# 1-7.net
KiCad netlist of a schematic drawn in EAGLE
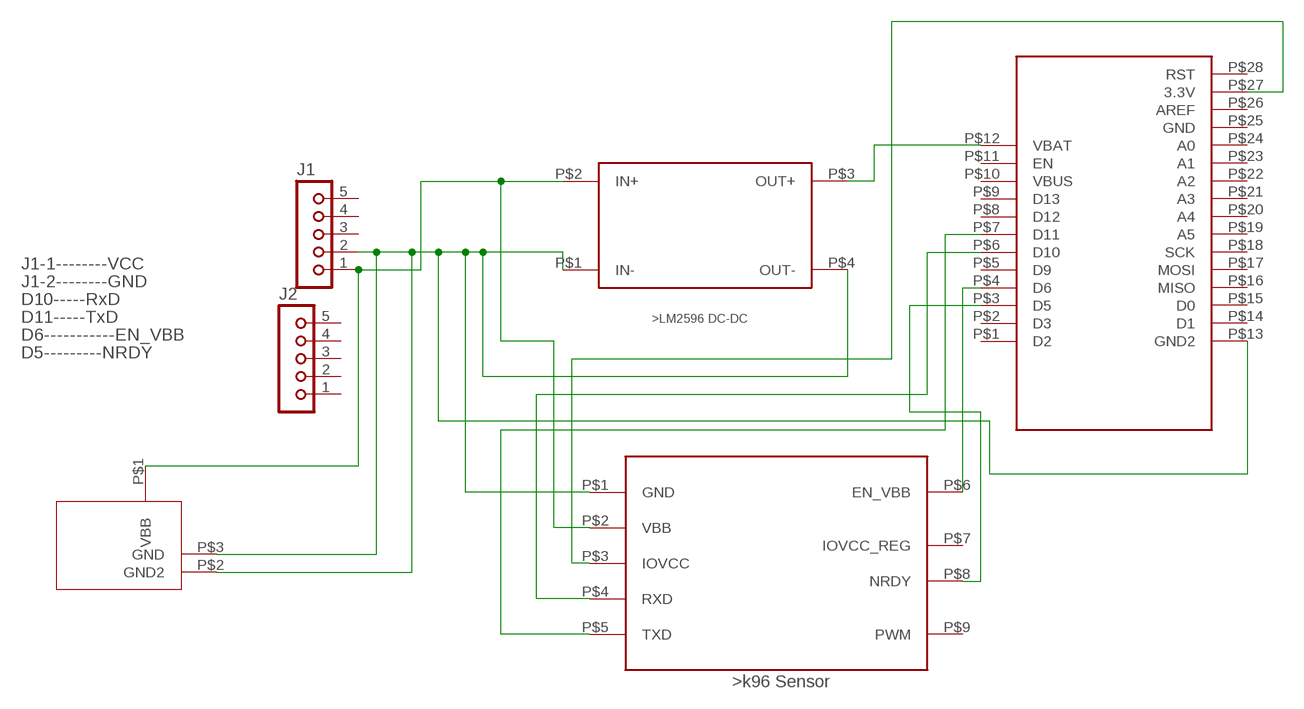
[diagram p0: schematic, sheet 1]

(export (version "E")
  (design (tool "Eeschema 10.0.6"))
  (components
    (comp (ref "DCDC1")
      (value "DCDC")
      (footprint "eagle-import:DCDC")
      (libsource (lib "eagle-import") (part "DCDC"))
    )
    (comp (ref "FEATHER1")
      (value "FEATHER")
      (footprint "eagle-import:FEATHER")
      (libsource (lib "eagle-import") (part "FEATHER"))
    )
    (comp (ref "J1")
      (value "JU05")
      (footprint "eagle-import:JU05")
      (libsource (lib "eagle-import") (part "JU05"))
    )
    (comp (ref "J2")
      (value "JU05")
      (footprint "eagle-import:JU05")
      (libsource (lib "eagle-import") (part "JU05"))
    )
    (comp (ref "K96SENSOR1")
      (value "K96SENSOR")
      (footprint "eagle-import:K96SENSOR")
      (libsource (lib "eagle-import") (part "K96SENSOR"))
    )
    (comp (ref "U$1")
      (value "POWER")
      (footprint "eagle-import:POWERIN")
      (libsource (lib "eagle-import") (part "POWER"))
    )
  )
  (nets
    (net (code "1") (name "Net-(DCDC1-IN+)") (class "Default")
      (node (ref "DCDC1") (pin "P$2") (pinfunction "IN+_P$2") (pintype "bidirectional"))
      (node (ref "J1") (pin "1") (pinfunction "1_1") (pintype "passive"))
      (node (ref "K96SENSOR1") (pin "P$2") (pinfunction "VBB_P$2") (pintype "bidirectional"))
      (node (ref "U$1") (pin "P$1") (pinfunction "VBB_P$1") (pintype "bidirectional"))
    )
    (net (code "2") (name "Net-(DCDC1-IN-)") (class "Default")
      (node (ref "DCDC1") (pin "P$1") (pinfunction "IN-_P$1") (pintype "bidirectional"))
      (node (ref "DCDC1") (pin "P$4") (pinfunction "OUT-_P$4") (pintype "bidirectional"))
      (node (ref "FEATHER1") (pin "P$13") (pinfunction "GND2_P$13") (pintype "bidirectional"))
      (node (ref "J1") (pin "2") (pinfunction "2_2") (pintype "passive"))
      (node (ref "K96SENSOR1") (pin "P$1") (pinfunction "GND_P$1") (pintype "bidirectional"))
      (node (ref "U$1") (pin "P$2") (pinfunction "GND2_P$2") (pintype "bidirectional"))
      (node (ref "U$1") (pin "P$3") (pinfunction "GND_P$3") (pintype "bidirectional"))
    )
    (net (code "3") (name "Net-(DCDC1-OUT+)") (class "Default")
      (node (ref "DCDC1") (pin "P$3") (pinfunction "OUT+_P$3") (pintype "bidirectional"))
      (node (ref "FEATHER1") (pin "P$12") (pinfunction "VBAT_P$12") (pintype "bidirectional"))
    )
    (net (code "4") (name "Net-(FEATHER1-3.3V)") (class "Default")
      (node (ref "FEATHER1") (pin "P$27") (pinfunction "3.3V_P$27") (pintype "bidirectional"))
      (node (ref "K96SENSOR1") (pin "P$3") (pinfunction "IOVCC_P$3") (pintype "bidirectional"))
    )
    (net (code "5") (name "Net-(FEATHER1-D5)") (class "Default")
      (node (ref "FEATHER1") (pin "P$3") (pinfunction "D5_P$3") (pintype "bidirectional"))
      (node (ref "K96SENSOR1") (pin "P$8") (pinfunction "NRDY_P$8") (pintype "bidirectional"))
    )
    (net (code "6") (name "Net-(FEATHER1-D6)") (class "Default")
      (node (ref "FEATHER1") (pin "P$4") (pinfunction "D6_P$4") (pintype "bidirectional"))
      (node (ref "K96SENSOR1") (pin "P$6") (pinfunction "EN_VBB_P$6") (pintype "bidirectional"))
    )
    (net (code "7") (name "Net-(FEATHER1-D10)") (class "Default")
      (node (ref "FEATHER1") (pin "P$6") (pinfunction "D10_P$6") (pintype "bidirectional"))
      (node (ref "K96SENSOR1") (pin "P$4") (pinfunction "RXD_P$4") (pintype "bidirectional"))
    )
    (net (code "8") (name "Net-(FEATHER1-D11)") (class "Default")
      (node (ref "FEATHER1") (pin "P$7") (pinfunction "D11_P$7") (pintype "bidirectional"))
      (node (ref "K96SENSOR1") (pin "P$5") (pinfunction "TXD_P$5") (pintype "bidirectional"))
    )
    (net (code "9") (name "unconnected-(FEATHER1-A0-PadP$24)") (class "Default")
      (node (ref "FEATHER1") (pin "P$24") (pinfunction "A0_P$24") (pintype "bidirectional"))
    )
    (net (code "10") (name "unconnected-(FEATHER1-A1-PadP$23)") (class "Default")
      (node (ref "FEATHER1") (pin "P$23") (pinfunction "A1_P$23") (pintype "bidirectional"))
    )
    (net (code "11") (name "unconnected-(FEATHER1-A2-PadP$22)") (class "Default")
      (node (ref "FEATHER1") (pin "P$22") (pinfunction "A2_P$22") (pintype "bidirectional"))
    )
    (net (code "12") (name "unconnected-(FEATHER1-A3-PadP$21)") (class "Default")
      (node (ref "FEATHER1") (pin "P$21") (pinfunction "A3_P$21") (pintype "bidirectional"))
    )
    (net (code "13") (name "unconnected-(FEATHER1-A4-PadP$20)") (class "Default")
      (node (ref "FEATHER1") (pin "P$20") (pinfunction "A4_P$20") (pintype "bidirectional"))
    )
    (net (code "14") (name "unconnected-(FEATHER1-A5-PadP$19)") (class "Default")
      (node (ref "FEATHER1") (pin "P$19") (pinfunction "A5_P$19") (pintype "bidirectional"))
    )
    (net (code "15") (name "unconnected-(FEATHER1-AREF-PadP$26)") (class "Default")
      (node (ref "FEATHER1") (pin "P$26") (pinfunction "AREF_P$26") (pintype "bidirectional"))
    )
    (net (code "16") (name "unconnected-(FEATHER1-D0-PadP$15)") (class "Default")
      (node (ref "FEATHER1") (pin "P$15") (pinfunction "D0_P$15") (pintype "bidirectional"))
    )
    (net (code "17") (name "unconnected-(FEATHER1-D1-PadP$14)") (class "Default")
      (node (ref "FEATHER1") (pin "P$14") (pinfunction "D1_P$14") (pintype "bidirectional"))
    )
    (net (code "18") (name "unconnected-(FEATHER1-D2-PadP$1)") (class "Default")
      (node (ref "FEATHER1") (pin "P$1") (pinfunction "D2_P$1") (pintype "bidirectional"))
    )
    (net (code "19") (name "unconnected-(FEATHER1-D3-PadP$2)") (class "Default")
      (node (ref "FEATHER1") (pin "P$2") (pinfunction "D3_P$2") (pintype "bidirectional"))
    )
    (net (code "20") (name "unconnected-(FEATHER1-D9-PadP$5)") (class "Default")
      (node (ref "FEATHER1") (pin "P$5") (pinfunction "D9_P$5") (pintype "bidirectional"))
    )
    (net (code "21") (name "unconnected-(FEATHER1-D12-PadP$8)") (class "Default")
      (node (ref "FEATHER1") (pin "P$8") (pinfunction "D12_P$8") (pintype "bidirectional"))
    )
    (net (code "22") (name "unconnected-(FEATHER1-D13-PadP$9)") (class "Default")
      (node (ref "FEATHER1") (pin "P$9") (pinfunction "D13_P$9") (pintype "bidirectional"))
    )
    (net (code "23") (name "unconnected-(FEATHER1-EN-PadP$11)") (class "Default")
      (node (ref "FEATHER1") (pin "P$11") (pinfunction "EN_P$11") (pintype "bidirectional"))
    )
    (net (code "24") (name "unconnected-(FEATHER1-GND-PadP$25)") (class "Default")
      (node (ref "FEATHER1") (pin "P$25") (pinfunction "GND_P$25") (pintype "bidirectional"))
    )
    (net (code "25") (name "unconnected-(FEATHER1-MISO-PadP$16)") (class "Default")
      (node (ref "FEATHER1") (pin "P$16") (pinfunction "MISO_P$16") (pintype "bidirectional"))
    )
    (net (code "26") (name "unconnected-(FEATHER1-MOSI-PadP$17)") (class "Default")
      (node (ref "FEATHER1") (pin "P$17") (pinfunction "MOSI_P$17") (pintype "bidirectional"))
    )
    (net (code "27") (name "unconnected-(FEATHER1-RST-PadP$28)") (class "Default")
      (node (ref "FEATHER1") (pin "P$28") (pinfunction "RST_P$28") (pintype "bidirectional"))
    )
    (net (code "28") (name "unconnected-(FEATHER1-SCK-PadP$18)") (class "Default")
      (node (ref "FEATHER1") (pin "P$18") (pinfunction "SCK_P$18") (pintype "bidirectional"))
    )
    (net (code "29") (name "unconnected-(FEATHER1-VBUS-PadP$10)") (class "Default")
      (node (ref "FEATHER1") (pin "P$10") (pinfunction "VBUS_P$10") (pintype "bidirectional"))
    )
    (net (code "30") (name "unconnected-(J1-Pad3)") (class "Default")
      (node (ref "J1") (pin "3") (pinfunction "3_3") (pintype "passive"))
    )
    (net (code "31") (name "unconnected-(J1-Pad4)") (class "Default")
      (node (ref "J1") (pin "4") (pinfunction "4_4") (pintype "passive"))
    )
    (net (code "32") (name "unconnected-(J1-Pad5)") (class "Default")
      (node (ref "J1") (pin "5") (pinfunction "5_5") (pintype "passive"))
    )
    (net (code "33") (name "unconnected-(J2-Pad1)") (class "Default")
      (node (ref "J2") (pin "1") (pinfunction "1_1") (pintype "passive"))
    )
    (net (code "34") (name "unconnected-(J2-Pad2)") (class "Default")
      (node (ref "J2") (pin "2") (pinfunction "2_2") (pintype "passive"))
    )
    (net (code "35") (name "unconnected-(J2-Pad3)") (class "Default")
      (node (ref "J2") (pin "3") (pinfunction "3_3") (pintype "passive"))
    )
    (net (code "36") (name "unconnected-(J2-Pad4)") (class "Default")
      (node (ref "J2") (pin "4") (pinfunction "4_4") (pintype "passive"))
    )
    (net (code "37") (name "unconnected-(J2-Pad5)") (class "Default")
      (node (ref "J2") (pin "5") (pinfunction "5_5") (pintype "passive"))
    )
    (net (code "38") (name "unconnected-(K96SENSOR1-IOVCC_REG-PadP$7)") (class "Default")
      (node (ref "K96SENSOR1") (pin "P$7") (pinfunction "IOVCC_REG_P$7") (pintype "bidirectional"))
    )
    (net (code "39") (name "unconnected-(K96SENSOR1-PWM-PadP$9)") (class "Default")
      (node (ref "K96SENSOR1") (pin "P$9") (pinfunction "PWM_P$9") (pintype "bidirectional"))
    )
  )
)
